# pro_mini_a7105_shield.net
KiCad netlist of a schematic drawn in EAGLE
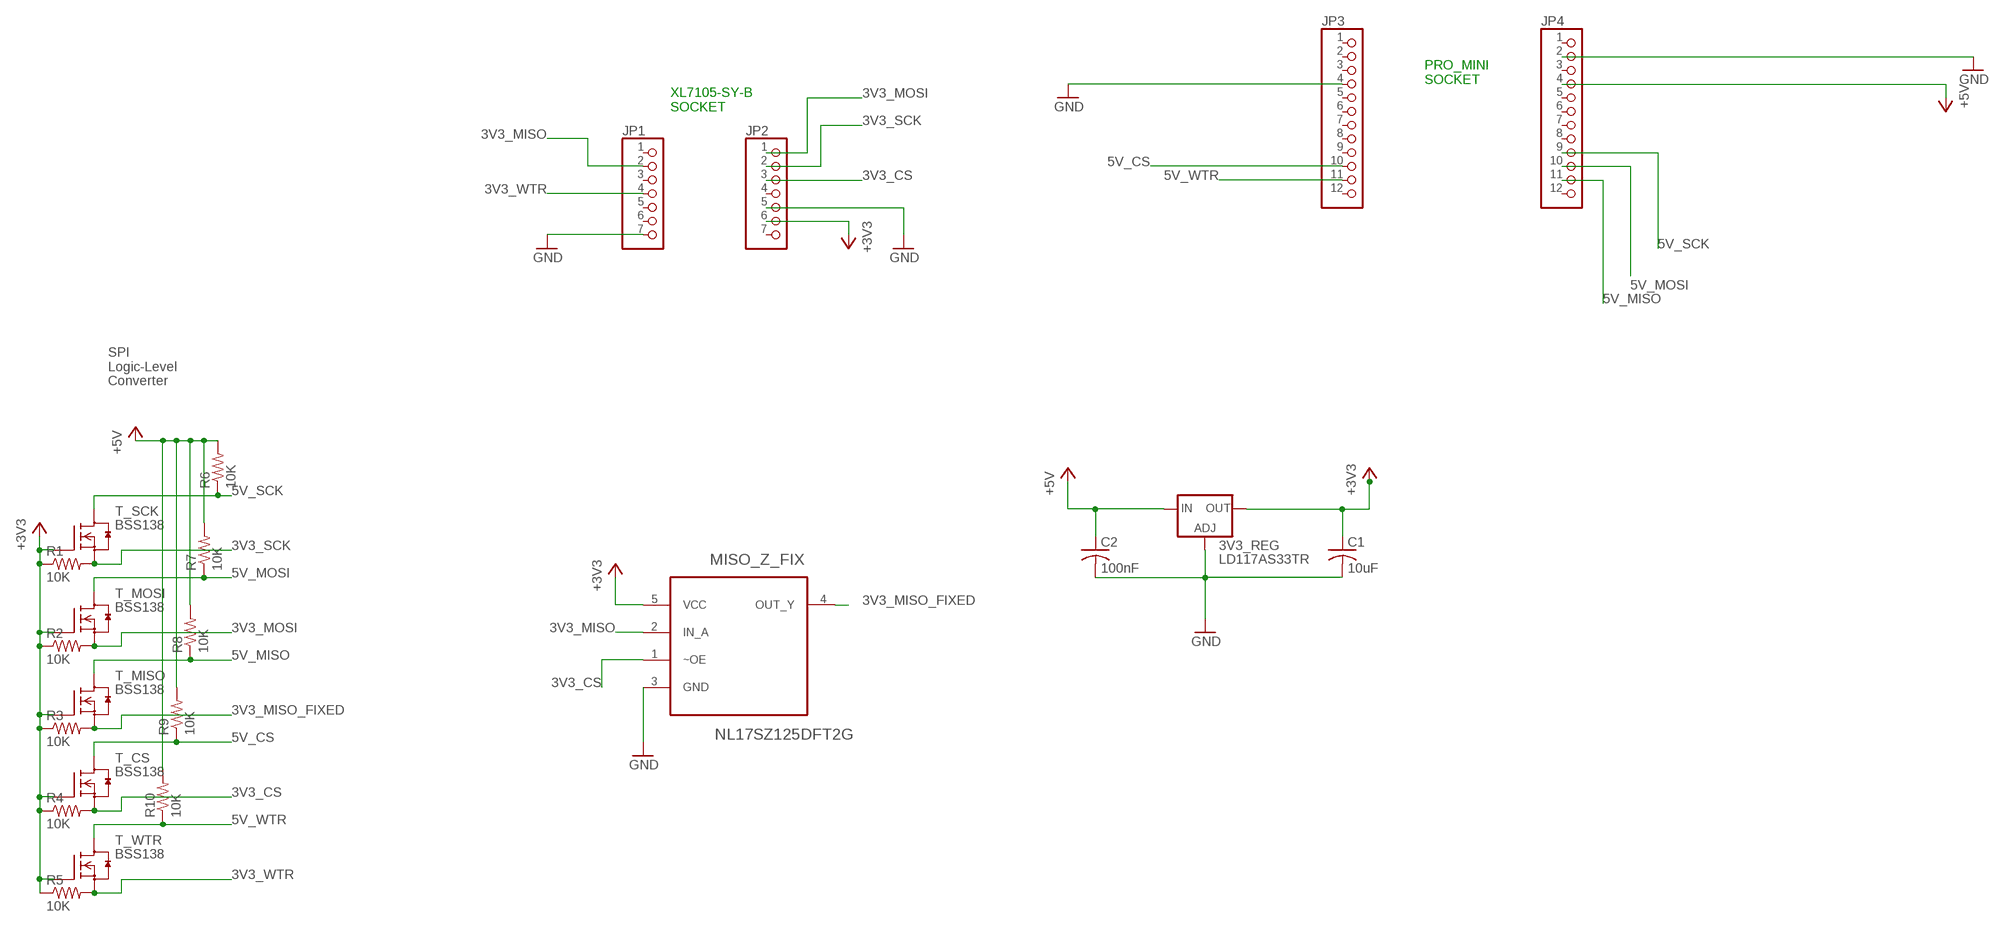
[diagram p0: schematic, sheet 1]

(export (version "E")
  (design (tool "Eeschema 10.0.6"))
  (components
    (comp (ref "3V3_REG")
      (value "LD117AS33TR")
      (footprint "eagle-import:SOT223")
      (libsource (lib "eagle-import") (part "LD117A?S33TR"))
    )
    (comp (ref "C1")
      (value "10uF")
      (footprint "eagle-import:C0805")
      (libsource (lib "eagle-import") (part "C-USC0805"))
    )
    (comp (ref "C2")
      (value "100nF")
      (footprint "eagle-import:C0805")
      (libsource (lib "eagle-import") (part "C-USC0805"))
    )
    (comp (ref "JP1")
      (value "PINHD-1X7M")
      (footprint "eagle-import:1X07M")
      (libsource (lib "eagle-import") (part "PINHD-1X7M"))
    )
    (comp (ref "JP2")
      (value "PINHD-1X7M")
      (footprint "eagle-import:1X07M")
      (libsource (lib "eagle-import") (part "PINHD-1X7M"))
    )
    (comp (ref "JP3")
      (value "PINHD-1X12")
      (footprint "eagle-import:1X12")
      (libsource (lib "eagle-import") (part "PINHD-1X12"))
    )
    (comp (ref "JP4")
      (value "PINHD-1X12")
      (footprint "eagle-import:1X12")
      (libsource (lib "eagle-import") (part "PINHD-1X12"))
    )
    (comp (ref "MISO_Z_FIX")
      (value "NL17SZ125DFT2G")
      (footprint "eagle-import:SOT65P210X110-5N")
      (libsource (lib "eagle-import") (part "NL17SZ125DFT2G"))
    )
    (comp (ref "R1")
      (value "10K")
      (footprint "eagle-import:R0805")
      (libsource (lib "eagle-import") (part "R-US_R0805"))
    )
    (comp (ref "R2")
      (value "10K")
      (footprint "eagle-import:R0805")
      (libsource (lib "eagle-import") (part "R-US_R0805"))
    )
    (comp (ref "R3")
      (value "10K")
      (footprint "eagle-import:R0805")
      (libsource (lib "eagle-import") (part "R-US_R0805"))
    )
    (comp (ref "R4")
      (value "10K")
      (footprint "eagle-import:R0805")
      (libsource (lib "eagle-import") (part "R-US_R0805"))
    )
    (comp (ref "R5")
      (value "10K")
      (footprint "eagle-import:R0805")
      (libsource (lib "eagle-import") (part "R-US_R0805"))
    )
    (comp (ref "R6")
      (value "10K")
      (footprint "eagle-import:R0805")
      (libsource (lib "eagle-import") (part "R-US_R0805"))
    )
    (comp (ref "R7")
      (value "10K")
      (footprint "eagle-import:R0805")
      (libsource (lib "eagle-import") (part "R-US_R0805"))
    )
    (comp (ref "R8")
      (value "10K")
      (footprint "eagle-import:R0805")
      (libsource (lib "eagle-import") (part "R-US_R0805"))
    )
    (comp (ref "R9")
      (value "10K")
      (footprint "eagle-import:R0805")
      (libsource (lib "eagle-import") (part "R-US_R0805"))
    )
    (comp (ref "R10")
      (value "10K")
      (footprint "eagle-import:R0805")
      (libsource (lib "eagle-import") (part "R-US_R0805"))
    )
    (comp (ref "T_CS")
      (value "BSS138")
      (footprint "eagle-import:SOT23")
      (libsource (lib "eagle-import") (part "BSS138"))
    )
    (comp (ref "T_MISO")
      (value "BSS138")
      (footprint "eagle-import:SOT23")
      (libsource (lib "eagle-import") (part "BSS138"))
    )
    (comp (ref "T_MOSI")
      (value "BSS138")
      (footprint "eagle-import:SOT23")
      (libsource (lib "eagle-import") (part "BSS138"))
    )
    (comp (ref "T_SCK")
      (value "BSS138")
      (footprint "eagle-import:SOT23")
      (libsource (lib "eagle-import") (part "BSS138"))
    )
    (comp (ref "T_WTR")
      (value "BSS138")
      (footprint "eagle-import:SOT23")
      (libsource (lib "eagle-import") (part "BSS138"))
    )
  )
  (nets
    (net (code "1") (name "+3V3") (class "Default")
      (node (ref "3V3_REG") (pin "4") (pinfunction "OUT_4") (pintype "passive"))
      (node (ref "C1") (pin "1") (pinfunction "1_1") (pintype "passive"))
      (node (ref "JP2") (pin "6") (pinfunction "6_6") (pintype "passive"))
      (node (ref "MISO_Z_FIX") (pin "5") (pinfunction "VCC_5") (pintype "power_in"))
      (node (ref "R1") (pin "1") (pinfunction "1_1") (pintype "passive"))
      (node (ref "R2") (pin "1") (pinfunction "1_1") (pintype "passive"))
      (node (ref "R3") (pin "1") (pinfunction "1_1") (pintype "passive"))
      (node (ref "R4") (pin "1") (pinfunction "1_1") (pintype "passive"))
      (node (ref "R5") (pin "1") (pinfunction "1_1") (pintype "passive"))
      (node (ref "T_CS") (pin "1") (pinfunction "G_1") (pintype "passive"))
      (node (ref "T_MISO") (pin "1") (pinfunction "G_1") (pintype "passive"))
      (node (ref "T_MOSI") (pin "1") (pinfunction "G_1") (pintype "passive"))
      (node (ref "T_SCK") (pin "1") (pinfunction "G_1") (pintype "passive"))
      (node (ref "T_WTR") (pin "1") (pinfunction "G_1") (pintype "passive"))
    )
    (net (code "2") (name "+5V") (class "Default")
      (node (ref "3V3_REG") (pin "3") (pinfunction "IN_3") (pintype "input"))
      (node (ref "C2") (pin "1") (pinfunction "1_1") (pintype "passive"))
      (node (ref "JP4") (pin "4") (pinfunction "4_4") (pintype "passive"))
      (node (ref "R10") (pin "2") (pinfunction "2_2") (pintype "passive"))
      (node (ref "R6") (pin "2") (pinfunction "2_2") (pintype "passive"))
      (node (ref "R7") (pin "2") (pinfunction "2_2") (pintype "passive"))
      (node (ref "R8") (pin "2") (pinfunction "2_2") (pintype "passive"))
      (node (ref "R9") (pin "2") (pinfunction "2_2") (pintype "passive"))
    )
    (net (code "3") (name "/3V3_CS") (class "Default")
      (node (ref "JP2") (pin "3") (pinfunction "3_3") (pintype "passive"))
      (node (ref "MISO_Z_FIX") (pin "1") (pinfunction "~{OE}_1") (pintype "input"))
      (node (ref "R4") (pin "2") (pinfunction "2_2") (pintype "passive"))
      (node (ref "T_CS") (pin "2") (pinfunction "S_2") (pintype "passive"))
    )
    (net (code "4") (name "/3V3_MISO") (class "Default")
      (node (ref "JP1") (pin "2") (pinfunction "2_2") (pintype "passive"))
      (node (ref "MISO_Z_FIX") (pin "2") (pinfunction "IN_A_2") (pintype "input"))
    )
    (net (code "5") (name "/3V3_MISO_FIXED") (class "Default")
      (node (ref "MISO_Z_FIX") (pin "4") (pinfunction "OUT_Y_4") (pintype "output"))
      (node (ref "R3") (pin "2") (pinfunction "2_2") (pintype "passive"))
      (node (ref "T_MISO") (pin "2") (pinfunction "S_2") (pintype "passive"))
    )
    (net (code "6") (name "/3V3_MOSI") (class "Default")
      (node (ref "JP2") (pin "1") (pinfunction "1_1") (pintype "passive"))
      (node (ref "R2") (pin "2") (pinfunction "2_2") (pintype "passive"))
      (node (ref "T_MOSI") (pin "2") (pinfunction "S_2") (pintype "passive"))
    )
    (net (code "7") (name "/3V3_SCK") (class "Default")
      (node (ref "JP2") (pin "2") (pinfunction "2_2") (pintype "passive"))
      (node (ref "R1") (pin "2") (pinfunction "2_2") (pintype "passive"))
      (node (ref "T_SCK") (pin "2") (pinfunction "S_2") (pintype "passive"))
    )
    (net (code "8") (name "/3V3_WTR") (class "Default")
      (node (ref "JP1") (pin "4") (pinfunction "4_4") (pintype "passive"))
      (node (ref "R5") (pin "2") (pinfunction "2_2") (pintype "passive"))
      (node (ref "T_WTR") (pin "2") (pinfunction "S_2") (pintype "passive"))
    )
    (net (code "9") (name "/5V_CS") (class "Default")
      (node (ref "JP3") (pin "10") (pinfunction "10_10") (pintype "passive"))
      (node (ref "R9") (pin "1") (pinfunction "1_1") (pintype "passive"))
      (node (ref "T_CS") (pin "3") (pinfunction "D_3") (pintype "passive"))
    )
    (net (code "10") (name "/5V_MISO") (class "Default")
      (node (ref "JP4") (pin "11") (pinfunction "11_11") (pintype "passive"))
      (node (ref "R8") (pin "1") (pinfunction "1_1") (pintype "passive"))
      (node (ref "T_MISO") (pin "3") (pinfunction "D_3") (pintype "passive"))
    )
    (net (code "11") (name "/5V_MOSI") (class "Default")
      (node (ref "JP4") (pin "10") (pinfunction "10_10") (pintype "passive"))
      (node (ref "R7") (pin "1") (pinfunction "1_1") (pintype "passive"))
      (node (ref "T_MOSI") (pin "3") (pinfunction "D_3") (pintype "passive"))
    )
    (net (code "12") (name "/5V_SCK") (class "Default")
      (node (ref "JP4") (pin "9") (pinfunction "9_9") (pintype "passive"))
      (node (ref "R6") (pin "1") (pinfunction "1_1") (pintype "passive"))
      (node (ref "T_SCK") (pin "3") (pinfunction "D_3") (pintype "passive"))
    )
    (net (code "13") (name "/5V_WTR") (class "Default")
      (node (ref "JP3") (pin "11") (pinfunction "11_11") (pintype "passive"))
      (node (ref "R10") (pin "1") (pinfunction "1_1") (pintype "passive"))
      (node (ref "T_WTR") (pin "3") (pinfunction "D_3") (pintype "passive"))
    )
    (net (code "14") (name "GND") (class "Default")
      (node (ref "3V3_REG") (pin "1") (pinfunction "ADJ_1") (pintype "input"))
      (node (ref "C1") (pin "2") (pinfunction "2_2") (pintype "passive"))
      (node (ref "C2") (pin "2") (pinfunction "2_2") (pintype "passive"))
      (node (ref "JP1") (pin "7") (pinfunction "7_7") (pintype "passive"))
      (node (ref "JP2") (pin "5") (pinfunction "5_5") (pintype "passive"))
      (node (ref "JP3") (pin "4") (pinfunction "4_4") (pintype "passive"))
      (node (ref "JP4") (pin "2") (pinfunction "2_2") (pintype "passive"))
      (node (ref "MISO_Z_FIX") (pin "3") (pinfunction "GND_3") (pintype "passive"))
    )
    (net (code "15") (name "unconnected-(JP1-Pad1)") (class "Default")
      (node (ref "JP1") (pin "1") (pinfunction "1_1") (pintype "passive"))
    )
    (net (code "16") (name "unconnected-(JP1-Pad3)") (class "Default")
      (node (ref "JP1") (pin "3") (pinfunction "3_3") (pintype "passive"))
    )
    (net (code "17") (name "unconnected-(JP1-Pad5)") (class "Default")
      (node (ref "JP1") (pin "5") (pinfunction "5_5") (pintype "passive"))
    )
    (net (code "18") (name "unconnected-(JP1-Pad6)") (class "Default")
      (node (ref "JP1") (pin "6") (pinfunction "6_6") (pintype "passive"))
    )
    (net (code "19") (name "unconnected-(JP2-Pad4)") (class "Default")
      (node (ref "JP2") (pin "4") (pinfunction "4_4") (pintype "passive"))
    )
    (net (code "20") (name "unconnected-(JP2-Pad7)") (class "Default")
      (node (ref "JP2") (pin "7") (pinfunction "7_7") (pintype "passive"))
    )
    (net (code "21") (name "unconnected-(JP3-Pad1)") (class "Default")
      (node (ref "JP3") (pin "1") (pinfunction "1_1") (pintype "passive"))
    )
    (net (code "22") (name "unconnected-(JP3-Pad2)") (class "Default")
      (node (ref "JP3") (pin "2") (pinfunction "2_2") (pintype "passive"))
    )
    (net (code "23") (name "unconnected-(JP3-Pad3)") (class "Default")
      (node (ref "JP3") (pin "3") (pinfunction "3_3") (pintype "passive"))
    )
    (net (code "24") (name "unconnected-(JP3-Pad5)") (class "Default")
      (node (ref "JP3") (pin "5") (pinfunction "5_5") (pintype "passive"))
    )
    (net (code "25") (name "unconnected-(JP3-Pad6)") (class "Default")
      (node (ref "JP3") (pin "6") (pinfunction "6_6") (pintype "passive"))
    )
    (net (code "26") (name "unconnected-(JP3-Pad7)") (class "Default")
      (node (ref "JP3") (pin "7") (pinfunction "7_7") (pintype "passive"))
    )
    (net (code "27") (name "unconnected-(JP3-Pad8)") (class "Default")
      (node (ref "JP3") (pin "8") (pinfunction "8_8") (pintype "passive"))
    )
    (net (code "28") (name "unconnected-(JP3-Pad9)") (class "Default")
      (node (ref "JP3") (pin "9") (pinfunction "9_9") (pintype "passive"))
    )
    (net (code "29") (name "unconnected-(JP3-Pad12)") (class "Default")
      (node (ref "JP3") (pin "12") (pinfunction "12_12") (pintype "passive"))
    )
    (net (code "30") (name "unconnected-(JP4-Pad1)") (class "Default")
      (node (ref "JP4") (pin "1") (pinfunction "1_1") (pintype "passive"))
    )
    (net (code "31") (name "unconnected-(JP4-Pad3)") (class "Default")
      (node (ref "JP4") (pin "3") (pinfunction "3_3") (pintype "passive"))
    )
    (net (code "32") (name "unconnected-(JP4-Pad5)") (class "Default")
      (node (ref "JP4") (pin "5") (pinfunction "5_5") (pintype "passive"))
    )
    (net (code "33") (name "unconnected-(JP4-Pad6)") (class "Default")
      (node (ref "JP4") (pin "6") (pinfunction "6_6") (pintype "passive"))
    )
    (net (code "34") (name "unconnected-(JP4-Pad7)") (class "Default")
      (node (ref "JP4") (pin "7") (pinfunction "7_7") (pintype "passive"))
    )
    (net (code "35") (name "unconnected-(JP4-Pad8)") (class "Default")
      (node (ref "JP4") (pin "8") (pinfunction "8_8") (pintype "passive"))
    )
    (net (code "36") (name "unconnected-(JP4-Pad12)") (class "Default")
      (node (ref "JP4") (pin "12") (pinfunction "12_12") (pintype "passive"))
    )
  )
)
